# 02A-001_Input_Switch.net
KiCad netlist of a schematic drawn in EAGLE
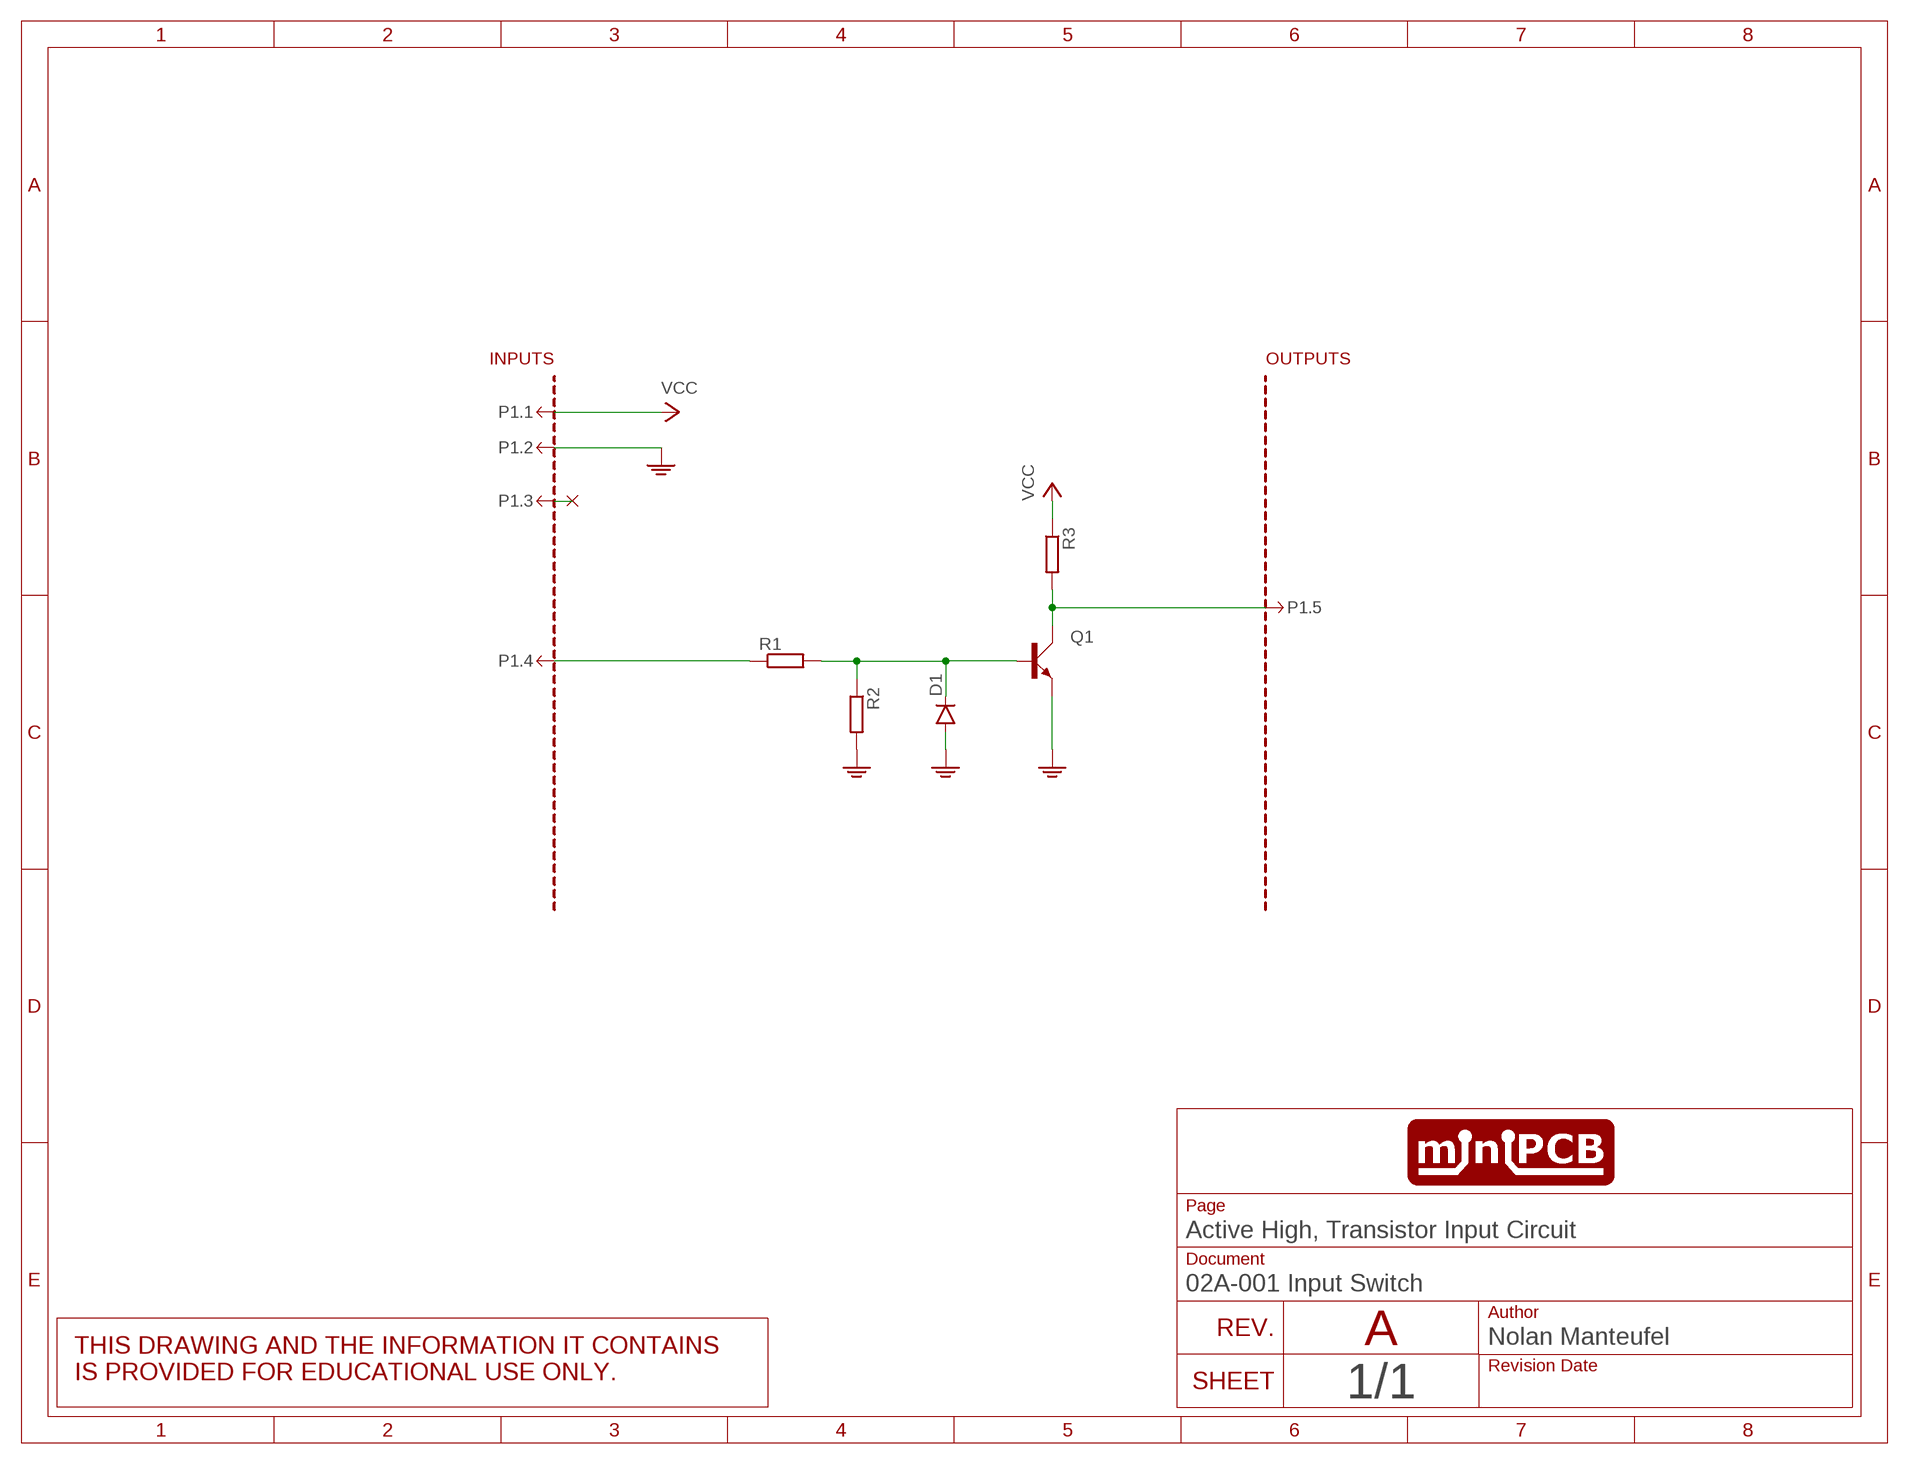
[diagram p0: schematic, sheet 1]

(export (version "E")
  (design (tool "Eeschema 10.0.6"))
  (components
    (comp (ref "D1")
      (value "DIODE-SOD80C")
      (footprint "eagle-import:SOD80C")
      (libsource (lib "eagle-import") (part "DIODE-SOD80C"))
    )
    (comp (ref "P1.")
      (value "MINIPCB_4INCH")
      (footprint "eagle-import:PCB_5")
      (libsource (lib "eagle-import") (part "MINIPCB_4INCH"))
    )
    (comp (ref "Q1")
      (value "BJT_NPNBEC")
      (footprint "eagle-import:SOT23")
      (libsource (lib "eagle-import") (part "BJT_NPNBEC"))
    )
    (comp (ref "R1")
      (value "R-EU_R0805")
      (footprint "eagle-import:R0805")
      (libsource (lib "eagle-import") (part "R-EU_R0805"))
    )
    (comp (ref "R2")
      (value "R-EU_R0805")
      (footprint "eagle-import:R0805")
      (libsource (lib "eagle-import") (part "R-EU_R0805"))
    )
    (comp (ref "R3")
      (value "R-EU_R0805")
      (footprint "eagle-import:R0805")
      (libsource (lib "eagle-import") (part "R-EU_R0805"))
    )
  )
  (nets
    (net (code "1") (name "GND") (class "Default")
      (node (ref "D1") (pin "A") (pinfunction "A_A") (pintype "passive"))
      (node (ref "P1.") (pin "1") (pinfunction "1_1") (pintype "bidirectional"))
      (node (ref "Q1") (pin "2") (pinfunction "E_2") (pintype "passive"))
      (node (ref "R2") (pin "2") (pinfunction "2_2") (pintype "passive"))
    )
    (net (code "2") (name "Net-(P1.D-1)") (class "Default")
      (node (ref "P1.") (pin "4") (pinfunction "1_4") (pintype "bidirectional"))
      (node (ref "R1") (pin "1") (pinfunction "1_1") (pintype "passive"))
    )
    (net (code "3") (name "Net-(P1.E-1)") (class "Default")
      (node (ref "P1.") (pin "5") (pinfunction "1_5") (pintype "bidirectional"))
      (node (ref "Q1") (pin "3") (pinfunction "C_3") (pintype "passive"))
      (node (ref "R3") (pin "2") (pinfunction "2_2") (pintype "passive"))
    )
    (net (code "4") (name "Net-(Q1-B)") (class "Default")
      (node (ref "D1") (pin "C") (pinfunction "C_C") (pintype "passive"))
      (node (ref "Q1") (pin "1") (pinfunction "B_1") (pintype "passive"))
      (node (ref "R1") (pin "2") (pinfunction "2_2") (pintype "passive"))
      (node (ref "R2") (pin "1") (pinfunction "1_1") (pintype "passive"))
    )
    (net (code "5") (name "VCC") (class "Default")
      (node (ref "P1.") (pin "2") (pinfunction "1_2") (pintype "bidirectional"))
      (node (ref "R3") (pin "1") (pinfunction "1_1") (pintype "passive"))
    )
    (net (code "6") (name "unconnected-(P1.C-1-Pad3)") (class "Default")
      (node (ref "P1.") (pin "3") (pinfunction "1_3") (pintype "bidirectional"))
    )
  )
)
